# 18_HD4_PUMP_2.net
KiCad netlist of a schematic drawn in Altium Designer
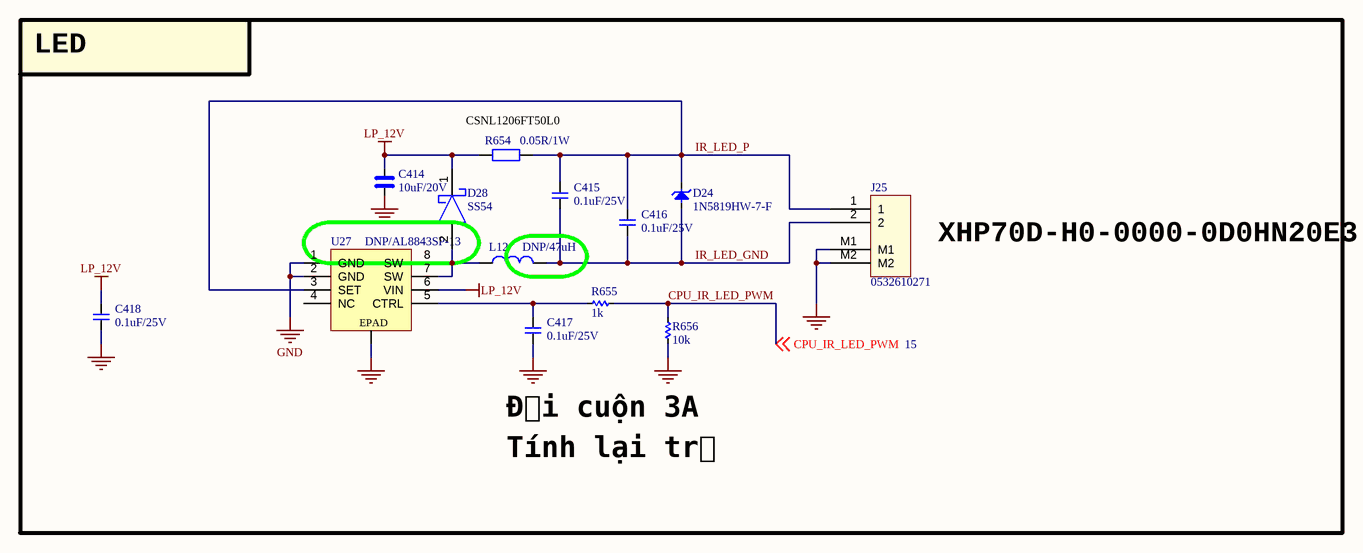
[diagram p0: 18_HD4_PUMP_2.SchDoc]

(export (version "E")
  (design (tool "Eeschema 10.0.6"))
  (components
    (comp (ref "C414")
      (value "10uF/20V")
      (footprint "CAP_C_2012X110")
      (description "CAP High Value")
      (libsource (lib "LABLIB") (part "_CAP_C_High_2"))
    )
    (comp (ref "C415")
      (value "0.1uF/25V")
      (footprint "CAP_C_1608X80")
      (description "CAP")
      (libsource (lib "LABLIB") (part "_CAP_C_2"))
    )
    (comp (ref "C416")
      (value "0.1uF/25V")
      (footprint "CAP_C_1608X80")
      (description "CAP")
      (libsource (lib "LABLIB") (part "_CAP_C_2"))
    )
    (comp (ref "C417")
      (value "0.1uF/25V")
      (footprint "CAP_C_1608X80")
      (description "CAP")
      (libsource (lib "LABLIB") (part "_CAP_C_2"))
    )
    (comp (ref "C418")
      (value "0.1uF/25V")
      (footprint "CAP_C_1608X80")
      (description "CAP")
      (libsource (lib "LABLIB") (part "_CAP_C_2"))
    )
    (comp (ref "D24")
      (value "1N5819HW-7-F")
      (footprint "SOD3717X145N")
      (description "Zenner")
      (libsource (lib "LABLIB") (part "DIODE Zener"))
    )
    (comp (ref "D28")
      (value "SS54")
      (footprint "DO-214AC_SMA")
      (description "DIODE SCHOTTKY 60V 3A DO214AA")
      (libsource (lib "EXP_HW_V3") (part "SS54"))
    )
    (comp (ref "J25")
      (value "0532610271")
      (footprint "MOLEX_5040500291")
      (libsource (lib "LABLIB") (part "Header 2x1_2M"))
    )
    (comp (ref "L12")
      (value "DNP/47uH")
      (footprint "IND_MP_1250x1250x850")
      (description "B82477P4473M000")
      (fields
        (field (name "PARTNO") "78477010")
        (field (name "MANUFACTURER") "Wurth Elektronik")
        (field (name "CREATED BY") "Baojun Chen")
      )
      (libsource (lib "EXP_HW_V3") (part "L-SMD-1"))
    )
    (comp (ref "R654")
      (value "0.05R/1W")
      (footprint "RES_C_3216X70")
      (description "RES")
      (libsource (lib "LABLIB") (part "_RES"))
    )
    (comp (ref "R655")
      (value "1k")
      (footprint "RES_C_1608X60")
      (description "RES")
      (libsource (lib "LABLIB") (part "_RES_B_2"))
    )
    (comp (ref "R656")
      (value "10k")
      (footprint "RES_C_1608X60")
      (description "RES")
      (libsource (lib "LABLIB") (part "_RES_B_2"))
    )
    (comp (ref "U27")
      (value "DNP/AL8843SP-13")
      (footprint "SOIC127P602X173-8N_EPAD")
      (description "IC LED DRIVER RGLTR PWM 3A 8SO")
      (libsource (lib "EXP_HW_V3") (part "AL8843SP-13"))
    )
  )
  (nets
    (net (code "1") (name "/IR_LED_GND") (class "Default")
      (node (ref "C415") (pin "1") (pinfunction "1_1") (pintype "passive"))
      (node (ref "C416") (pin "1") (pinfunction "1_1") (pintype "passive"))
      (node (ref "D24") (pin "2") (pinfunction "A_2") (pintype "passive"))
      (node (ref "J25") (pin "2") (pinfunction "2_2") (pintype "passive"))
      (node (ref "L12") (pin "2") (pinfunction "2_2") (pintype "passive"))
    )
    (net (code "2") (name "/IR_LED_P") (class "Default")
      (node (ref "C415") (pin "2") (pinfunction "2_2") (pintype "passive"))
      (node (ref "C416") (pin "2") (pinfunction "2_2") (pintype "passive"))
      (node (ref "D24") (pin "1") (pinfunction "K_1") (pintype "passive"))
      (node (ref "J25") (pin "1") (pinfunction "1_1") (pintype "passive"))
      (node (ref "R654") (pin "2") (pinfunction "2_2") (pintype "passive"))
      (node (ref "U27") (pin "3") (pinfunction "SET_3") (pintype "passive"))
    )
    (net (code "3") (name "CPU_IR_LED_PWM") (class "Default")
      (node (ref "R655") (pin "2") (pinfunction "2_2") (pintype "passive"))
      (node (ref "R656") (pin "1") (pinfunction "1_1") (pintype "passive"))
    )
    (net (code "4") (name "GND") (class "Default")
      (node (ref "C414") (pin "2") (pinfunction "2_2") (pintype "passive"))
      (node (ref "C417") (pin "1") (pinfunction "1_1") (pintype "passive"))
      (node (ref "C418") (pin "1") (pinfunction "1_1") (pintype "passive"))
      (node (ref "J25") (pin "M1") (pinfunction "M1_M1") (pintype "passive"))
      (node (ref "J25") (pin "M2") (pinfunction "M2_M2") (pintype "passive"))
      (node (ref "R656") (pin "2") (pinfunction "2_2") (pintype "passive"))
      (node (ref "U27") (pin "1") (pinfunction "GND_1") (pintype "passive"))
      (node (ref "U27") (pin "2") (pinfunction "GND_2") (pintype "passive"))
      (node (ref "U27") (pin "9") (pinfunction "EPAD_9") (pintype "passive"))
    )
    (net (code "5") (name "LP_12V") (class "Default")
      (node (ref "C414") (pin "1") (pinfunction "1_1") (pintype "passive"))
      (node (ref "C418") (pin "2") (pinfunction "2_2") (pintype "passive"))
      (node (ref "D28") (pin "1") (pinfunction "1_1") (pintype "passive"))
      (node (ref "R654") (pin "1") (pinfunction "1_1") (pintype "passive"))
      (node (ref "U27") (pin "6") (pinfunction "VIN_6") (pintype "passive"))
    )
    (net (code "6") (name "Net-(D28-Pad2)") (class "Default")
      (node (ref "D28") (pin "2") (pinfunction "2_2") (pintype "passive"))
      (node (ref "L12") (pin "1") (pinfunction "1_1") (pintype "passive"))
      (node (ref "U27") (pin "7") (pinfunction "SW_7") (pintype "passive"))
      (node (ref "U27") (pin "8") (pinfunction "SW_8") (pintype "passive"))
    )
    (net (code "7") (name "Net-(U27-CTRL)") (class "Default")
      (node (ref "C417") (pin "2") (pinfunction "2_2") (pintype "passive"))
      (node (ref "R655") (pin "1") (pinfunction "1_1") (pintype "passive"))
      (node (ref "U27") (pin "5") (pinfunction "CTRL_5") (pintype "passive"))
    )
    (net (code "8") (name "unconnected-(U27-NC-Pad4)") (class "Default")
      (node (ref "U27") (pin "4") (pinfunction "NC_4") (pintype "passive"))
    )
  )
)
